# probe.net
KiCad netlist of a schematic drawn in Altium Designer
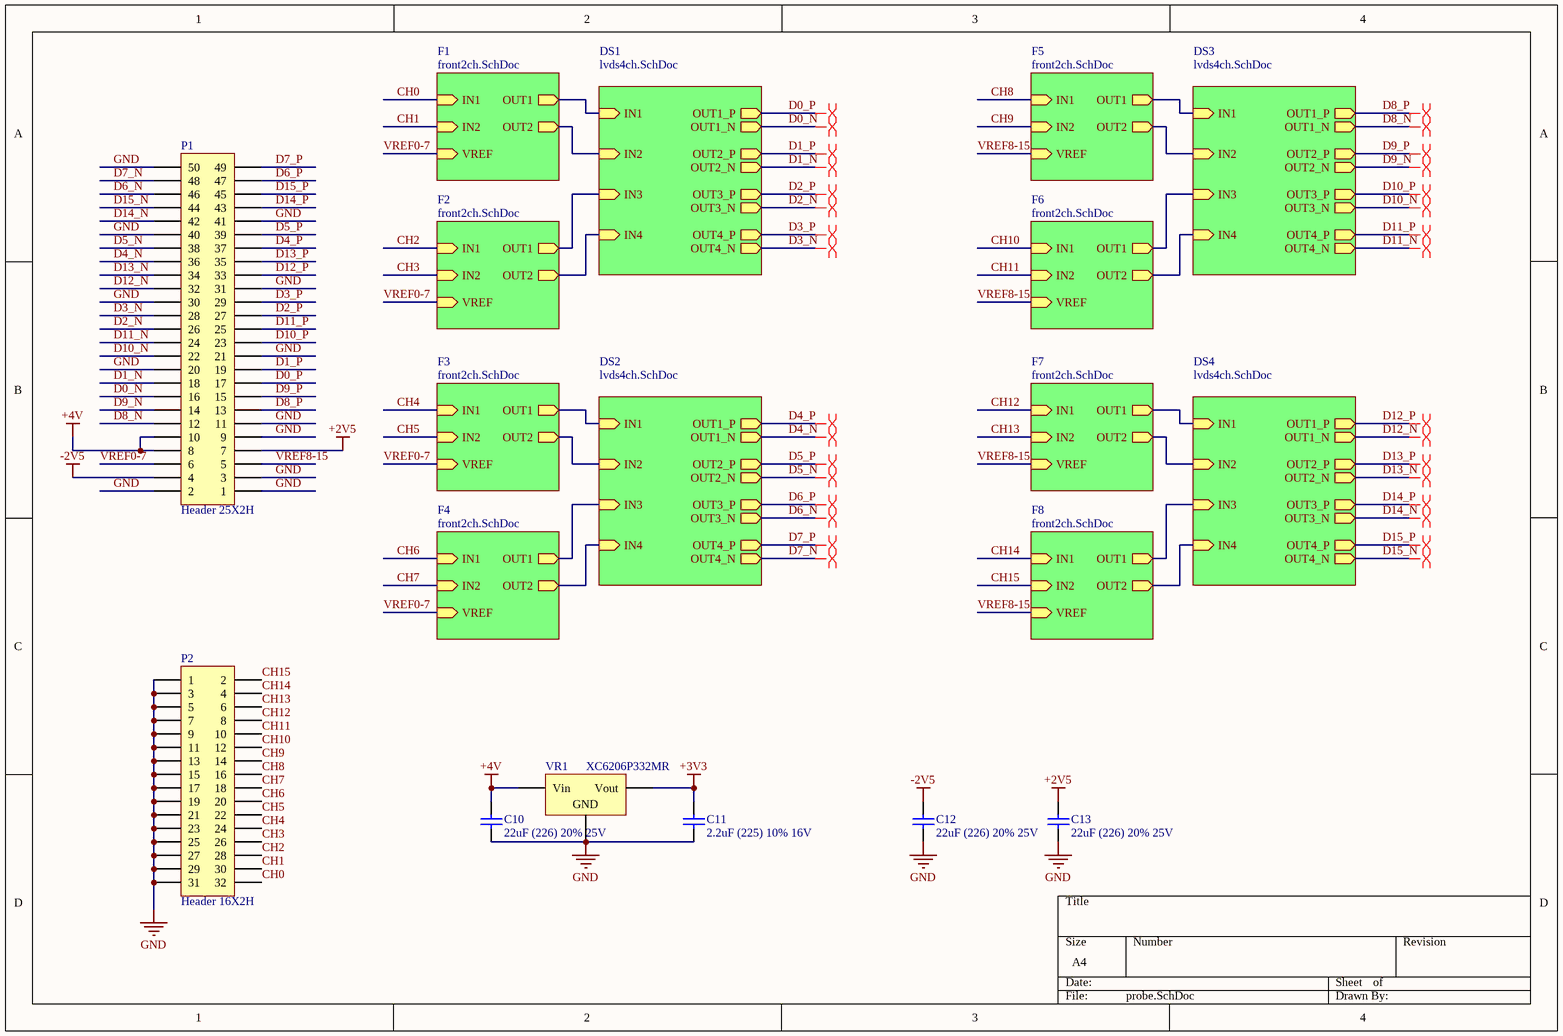
[diagram p0: probe.SchDoc]

(export (version "E")
  (design (tool "Eeschema 10.0.6"))
  (components
    (comp (ref "C10")
      (value "22uF (226) 20% 25V")
      (footprint "0805_C")
      (description "贴片电容")
      (libsource (lib "Miscellaneous Devices LC") (part "0805 22uF (226) 20% 25V"))
    )
    (comp (ref "C11")
      (value "2.2uF (225) 10% 16V")
      (footprint "0603_C")
      (description "贴片电容")
      (libsource (lib "Miscellaneous Devices LC") (part "0603 2.2uF (225) 10% 16V"))
    )
    (comp (ref "C12")
      (value "22uF (226) 20% 25V")
      (footprint "0805_C")
      (description "贴片电容")
      (libsource (lib "Miscellaneous Devices LC") (part "0805 22uF (226) 20% 25V"))
    )
    (comp (ref "C13")
      (value "22uF (226) 20% 25V")
      (footprint "0805_C")
      (description "贴片电容")
      (libsource (lib "Miscellaneous Devices LC") (part "0805 22uF (226) 20% 25V"))
    )
    (comp (ref "P1")
      (value "Header 25X2H")
      (footprint "HDR2X25H")
      (description "Header, 25-Pin, Dual row, Right Angle")
      (fields (field (name "PUBLISHER") "Altium Limited"))
      (libsource (lib "Miscellaneous Connectors") (part "Header 25X2H"))
    )
    (comp (ref "P2")
      (value "Header 16X2H")
      (footprint "HDR2X16H")
      (description "Header, 16-Pin, Dual row, Right Angle")
      (fields (field (name "PUBLISHER") "Altium Limited"))
      (libsource (lib "Miscellaneous Connectors") (part "Header 16X2H"))
    )
    (comp (ref "VR1")
      (value "XC6206P332MR")
      (footprint "SOT-23-3L")
      (description "低压差线性稳压(LDO)")
      (libsource (lib "Miscellaneous Devices LC") (part "SOT-23 XC6206P332MR"))
    )
  )
  (nets
    (net (code "1") (name "+2V5") (class "Default")
      (node (ref "C13") (pin "2") (pinfunction "2_2") (pintype "passive"))
      (node (ref "P1") (pin "7") (pinfunction "7_7") (pintype "passive"))
    )
    (net (code "2") (name "+3V3") (class "Default")
      (node (ref "C11") (pin "2") (pinfunction "2_2") (pintype "passive"))
      (node (ref "VR1") (pin "2") (pinfunction "Vout_2") (pintype "passive"))
    )
    (net (code "3") (name "+4V") (class "Default")
      (node (ref "C10") (pin "2") (pinfunction "2_2") (pintype "passive"))
      (node (ref "P1") (pin "10") (pinfunction "10_10") (pintype "passive"))
      (node (ref "P1") (pin "8") (pinfunction "8_8") (pintype "passive"))
      (node (ref "VR1") (pin "3") (pinfunction "Vin_3") (pintype "passive"))
    )
    (net (code "4") (name "-2V5") (class "Default")
      (node (ref "C12") (pin "2") (pinfunction "2_2") (pintype "passive"))
      (node (ref "P1") (pin "4") (pinfunction "4_4") (pintype "passive"))
    )
    (net (code "5") (name "/CH0") (class "Default")
      (node (ref "P2") (pin "32") (pinfunction "32_32") (pintype "passive"))
    )
    (net (code "6") (name "/CH1") (class "Default")
      (node (ref "P2") (pin "30") (pinfunction "30_30") (pintype "passive"))
    )
    (net (code "7") (name "/CH2") (class "Default")
      (node (ref "P2") (pin "28") (pinfunction "28_28") (pintype "passive"))
    )
    (net (code "8") (name "/CH3") (class "Default")
      (node (ref "P2") (pin "26") (pinfunction "26_26") (pintype "passive"))
    )
    (net (code "9") (name "/CH4") (class "Default")
      (node (ref "P2") (pin "24") (pinfunction "24_24") (pintype "passive"))
    )
    (net (code "10") (name "/CH5") (class "Default")
      (node (ref "P2") (pin "22") (pinfunction "22_22") (pintype "passive"))
    )
    (net (code "11") (name "/CH6") (class "Default")
      (node (ref "P2") (pin "20") (pinfunction "20_20") (pintype "passive"))
    )
    (net (code "12") (name "/CH7") (class "Default")
      (node (ref "P2") (pin "18") (pinfunction "18_18") (pintype "passive"))
    )
    (net (code "13") (name "/CH8") (class "Default")
      (node (ref "P2") (pin "16") (pinfunction "16_16") (pintype "passive"))
    )
    (net (code "14") (name "/CH9") (class "Default")
      (node (ref "P2") (pin "14") (pinfunction "14_14") (pintype "passive"))
    )
    (net (code "15") (name "/CH10") (class "Default")
      (node (ref "P2") (pin "12") (pinfunction "12_12") (pintype "passive"))
    )
    (net (code "16") (name "/CH11") (class "Default")
      (node (ref "P2") (pin "10") (pinfunction "10_10") (pintype "passive"))
    )
    (net (code "17") (name "/CH12") (class "Default")
      (node (ref "P2") (pin "8") (pinfunction "8_8") (pintype "passive"))
    )
    (net (code "18") (name "/CH13") (class "Default")
      (node (ref "P2") (pin "6") (pinfunction "6_6") (pintype "passive"))
    )
    (net (code "19") (name "/CH14") (class "Default")
      (node (ref "P2") (pin "4") (pinfunction "4_4") (pintype "passive"))
    )
    (net (code "20") (name "/CH15") (class "Default")
      (node (ref "P2") (pin "2") (pinfunction "2_2") (pintype "passive"))
    )
    (net (code "21") (name "/D0_N") (class "Default")
      (node (ref "P1") (pin "16") (pinfunction "16_16") (pintype "passive"))
    )
    (net (code "22") (name "/D0_P") (class "Default")
      (node (ref "P1") (pin "17") (pinfunction "17_17") (pintype "passive"))
    )
    (net (code "23") (name "/D1_N") (class "Default")
      (node (ref "P1") (pin "18") (pinfunction "18_18") (pintype "passive"))
    )
    (net (code "24") (name "/D1_P") (class "Default")
      (node (ref "P1") (pin "19") (pinfunction "19_19") (pintype "passive"))
    )
    (net (code "25") (name "/D2_N") (class "Default")
      (node (ref "P1") (pin "26") (pinfunction "26_26") (pintype "passive"))
    )
    (net (code "26") (name "/D2_P") (class "Default")
      (node (ref "P1") (pin "27") (pinfunction "27_27") (pintype "passive"))
    )
    (net (code "27") (name "/D3_N") (class "Default")
      (node (ref "P1") (pin "28") (pinfunction "28_28") (pintype "passive"))
    )
    (net (code "28") (name "/D3_P") (class "Default")
      (node (ref "P1") (pin "29") (pinfunction "29_29") (pintype "passive"))
    )
    (net (code "29") (name "/D4_N") (class "Default")
      (node (ref "P1") (pin "36") (pinfunction "36_36") (pintype "passive"))
    )
    (net (code "30") (name "/D4_P") (class "Default")
      (node (ref "P1") (pin "37") (pinfunction "37_37") (pintype "passive"))
    )
    (net (code "31") (name "/D5_N") (class "Default")
      (node (ref "P1") (pin "38") (pinfunction "38_38") (pintype "passive"))
    )
    (net (code "32") (name "/D5_P") (class "Default")
      (node (ref "P1") (pin "39") (pinfunction "39_39") (pintype "passive"))
    )
    (net (code "33") (name "/D6_N") (class "Default")
      (node (ref "P1") (pin "46") (pinfunction "46_46") (pintype "passive"))
    )
    (net (code "34") (name "/D6_P") (class "Default")
      (node (ref "P1") (pin "47") (pinfunction "47_47") (pintype "passive"))
    )
    (net (code "35") (name "/D7_N") (class "Default")
      (node (ref "P1") (pin "48") (pinfunction "48_48") (pintype "passive"))
    )
    (net (code "36") (name "/D7_P") (class "Default")
      (node (ref "P1") (pin "49") (pinfunction "49_49") (pintype "passive"))
    )
    (net (code "37") (name "/D8_N") (class "Default")
      (node (ref "P1") (pin "12") (pinfunction "12_12") (pintype "passive"))
    )
    (net (code "38") (name "/D8_P") (class "Default")
      (node (ref "P1") (pin "13") (pinfunction "13_13") (pintype "passive"))
    )
    (net (code "39") (name "/D9_N") (class "Default")
      (node (ref "P1") (pin "14") (pinfunction "14_14") (pintype "passive"))
    )
    (net (code "40") (name "/D9_P") (class "Default")
      (node (ref "P1") (pin "15") (pinfunction "15_15") (pintype "passive"))
    )
    (net (code "41") (name "/D10_N") (class "Default")
      (node (ref "P1") (pin "22") (pinfunction "22_22") (pintype "passive"))
    )
    (net (code "42") (name "/D10_P") (class "Default")
      (node (ref "P1") (pin "23") (pinfunction "23_23") (pintype "passive"))
    )
    (net (code "43") (name "/D11_N") (class "Default")
      (node (ref "P1") (pin "24") (pinfunction "24_24") (pintype "passive"))
    )
    (net (code "44") (name "/D11_P") (class "Default")
      (node (ref "P1") (pin "25") (pinfunction "25_25") (pintype "passive"))
    )
    (net (code "45") (name "/D12_N") (class "Default")
      (node (ref "P1") (pin "32") (pinfunction "32_32") (pintype "passive"))
    )
    (net (code "46") (name "/D12_P") (class "Default")
      (node (ref "P1") (pin "33") (pinfunction "33_33") (pintype "passive"))
    )
    (net (code "47") (name "/D13_N") (class "Default")
      (node (ref "P1") (pin "34") (pinfunction "34_34") (pintype "passive"))
    )
    (net (code "48") (name "/D13_P") (class "Default")
      (node (ref "P1") (pin "35") (pinfunction "35_35") (pintype "passive"))
    )
    (net (code "49") (name "/D14_N") (class "Default")
      (node (ref "P1") (pin "42") (pinfunction "42_42") (pintype "passive"))
    )
    (net (code "50") (name "/D14_P") (class "Default")
      (node (ref "P1") (pin "43") (pinfunction "43_43") (pintype "passive"))
    )
    (net (code "51") (name "/D15_N") (class "Default")
      (node (ref "P1") (pin "44") (pinfunction "44_44") (pintype "passive"))
    )
    (net (code "52") (name "/D15_P") (class "Default")
      (node (ref "P1") (pin "45") (pinfunction "45_45") (pintype "passive"))
    )
    (net (code "69") (name "/VREF0-7") (class "Default")
      (node (ref "P1") (pin "6") (pinfunction "6_6") (pintype "passive"))
    )
    (net (code "70") (name "/VREF8-15") (class "Default")
      (node (ref "P1") (pin "5") (pinfunction "5_5") (pintype "passive"))
    )
    (net (code "71") (name "GND") (class "Default")
      (node (ref "C10") (pin "1") (pinfunction "1_1") (pintype "passive"))
      (node (ref "C11") (pin "1") (pinfunction "1_1") (pintype "passive"))
      (node (ref "C12") (pin "1") (pinfunction "1_1") (pintype "passive"))
      (node (ref "C13") (pin "1") (pinfunction "1_1") (pintype "passive"))
      (node (ref "P1") (pin "1") (pinfunction "1_1") (pintype "passive"))
      (node (ref "P1") (pin "11") (pinfunction "11_11") (pintype "passive"))
      (node (ref "P1") (pin "2") (pinfunction "2_2") (pintype "passive"))
      (node (ref "P1") (pin "20") (pinfunction "20_20") (pintype "passive"))
      (node (ref "P1") (pin "21") (pinfunction "21_21") (pintype "passive"))
      (node (ref "P1") (pin "3") (pinfunction "3_3") (pintype "passive"))
      (node (ref "P1") (pin "30") (pinfunction "30_30") (pintype "passive"))
      (node (ref "P1") (pin "31") (pinfunction "31_31") (pintype "passive"))
      (node (ref "P1") (pin "40") (pinfunction "40_40") (pintype "passive"))
      (node (ref "P1") (pin "41") (pinfunction "41_41") (pintype "passive"))
      (node (ref "P1") (pin "50") (pinfunction "50_50") (pintype "passive"))
      (node (ref "P1") (pin "9") (pinfunction "9_9") (pintype "passive"))
      (node (ref "P2") (pin "1") (pinfunction "1_1") (pintype "passive"))
      (node (ref "P2") (pin "11") (pinfunction "11_11") (pintype "passive"))
      (node (ref "P2") (pin "13") (pinfunction "13_13") (pintype "passive"))
      (node (ref "P2") (pin "15") (pinfunction "15_15") (pintype "passive"))
      (node (ref "P2") (pin "17") (pinfunction "17_17") (pintype "passive"))
      (node (ref "P2") (pin "19") (pinfunction "19_19") (pintype "passive"))
      (node (ref "P2") (pin "21") (pinfunction "21_21") (pintype "passive"))
      (node (ref "P2") (pin "23") (pinfunction "23_23") (pintype "passive"))
      (node (ref "P2") (pin "25") (pinfunction "25_25") (pintype "passive"))
      (node (ref "P2") (pin "27") (pinfunction "27_27") (pintype "passive"))
      (node (ref "P2") (pin "29") (pinfunction "29_29") (pintype "passive"))
      (node (ref "P2") (pin "3") (pinfunction "3_3") (pintype "passive"))
      (node (ref "P2") (pin "31") (pinfunction "31_31") (pintype "passive"))
      (node (ref "P2") (pin "5") (pinfunction "5_5") (pintype "passive"))
      (node (ref "P2") (pin "7") (pinfunction "7_7") (pintype "passive"))
      (node (ref "P2") (pin "9") (pinfunction "9_9") (pintype "passive"))
      (node (ref "VR1") (pin "1") (pinfunction "GND_1") (pintype "passive"))
    )
  )
)
